# EEE314_PIC32540_Programmer.net
KiCad netlist of a schematic drawn in Altium Designer
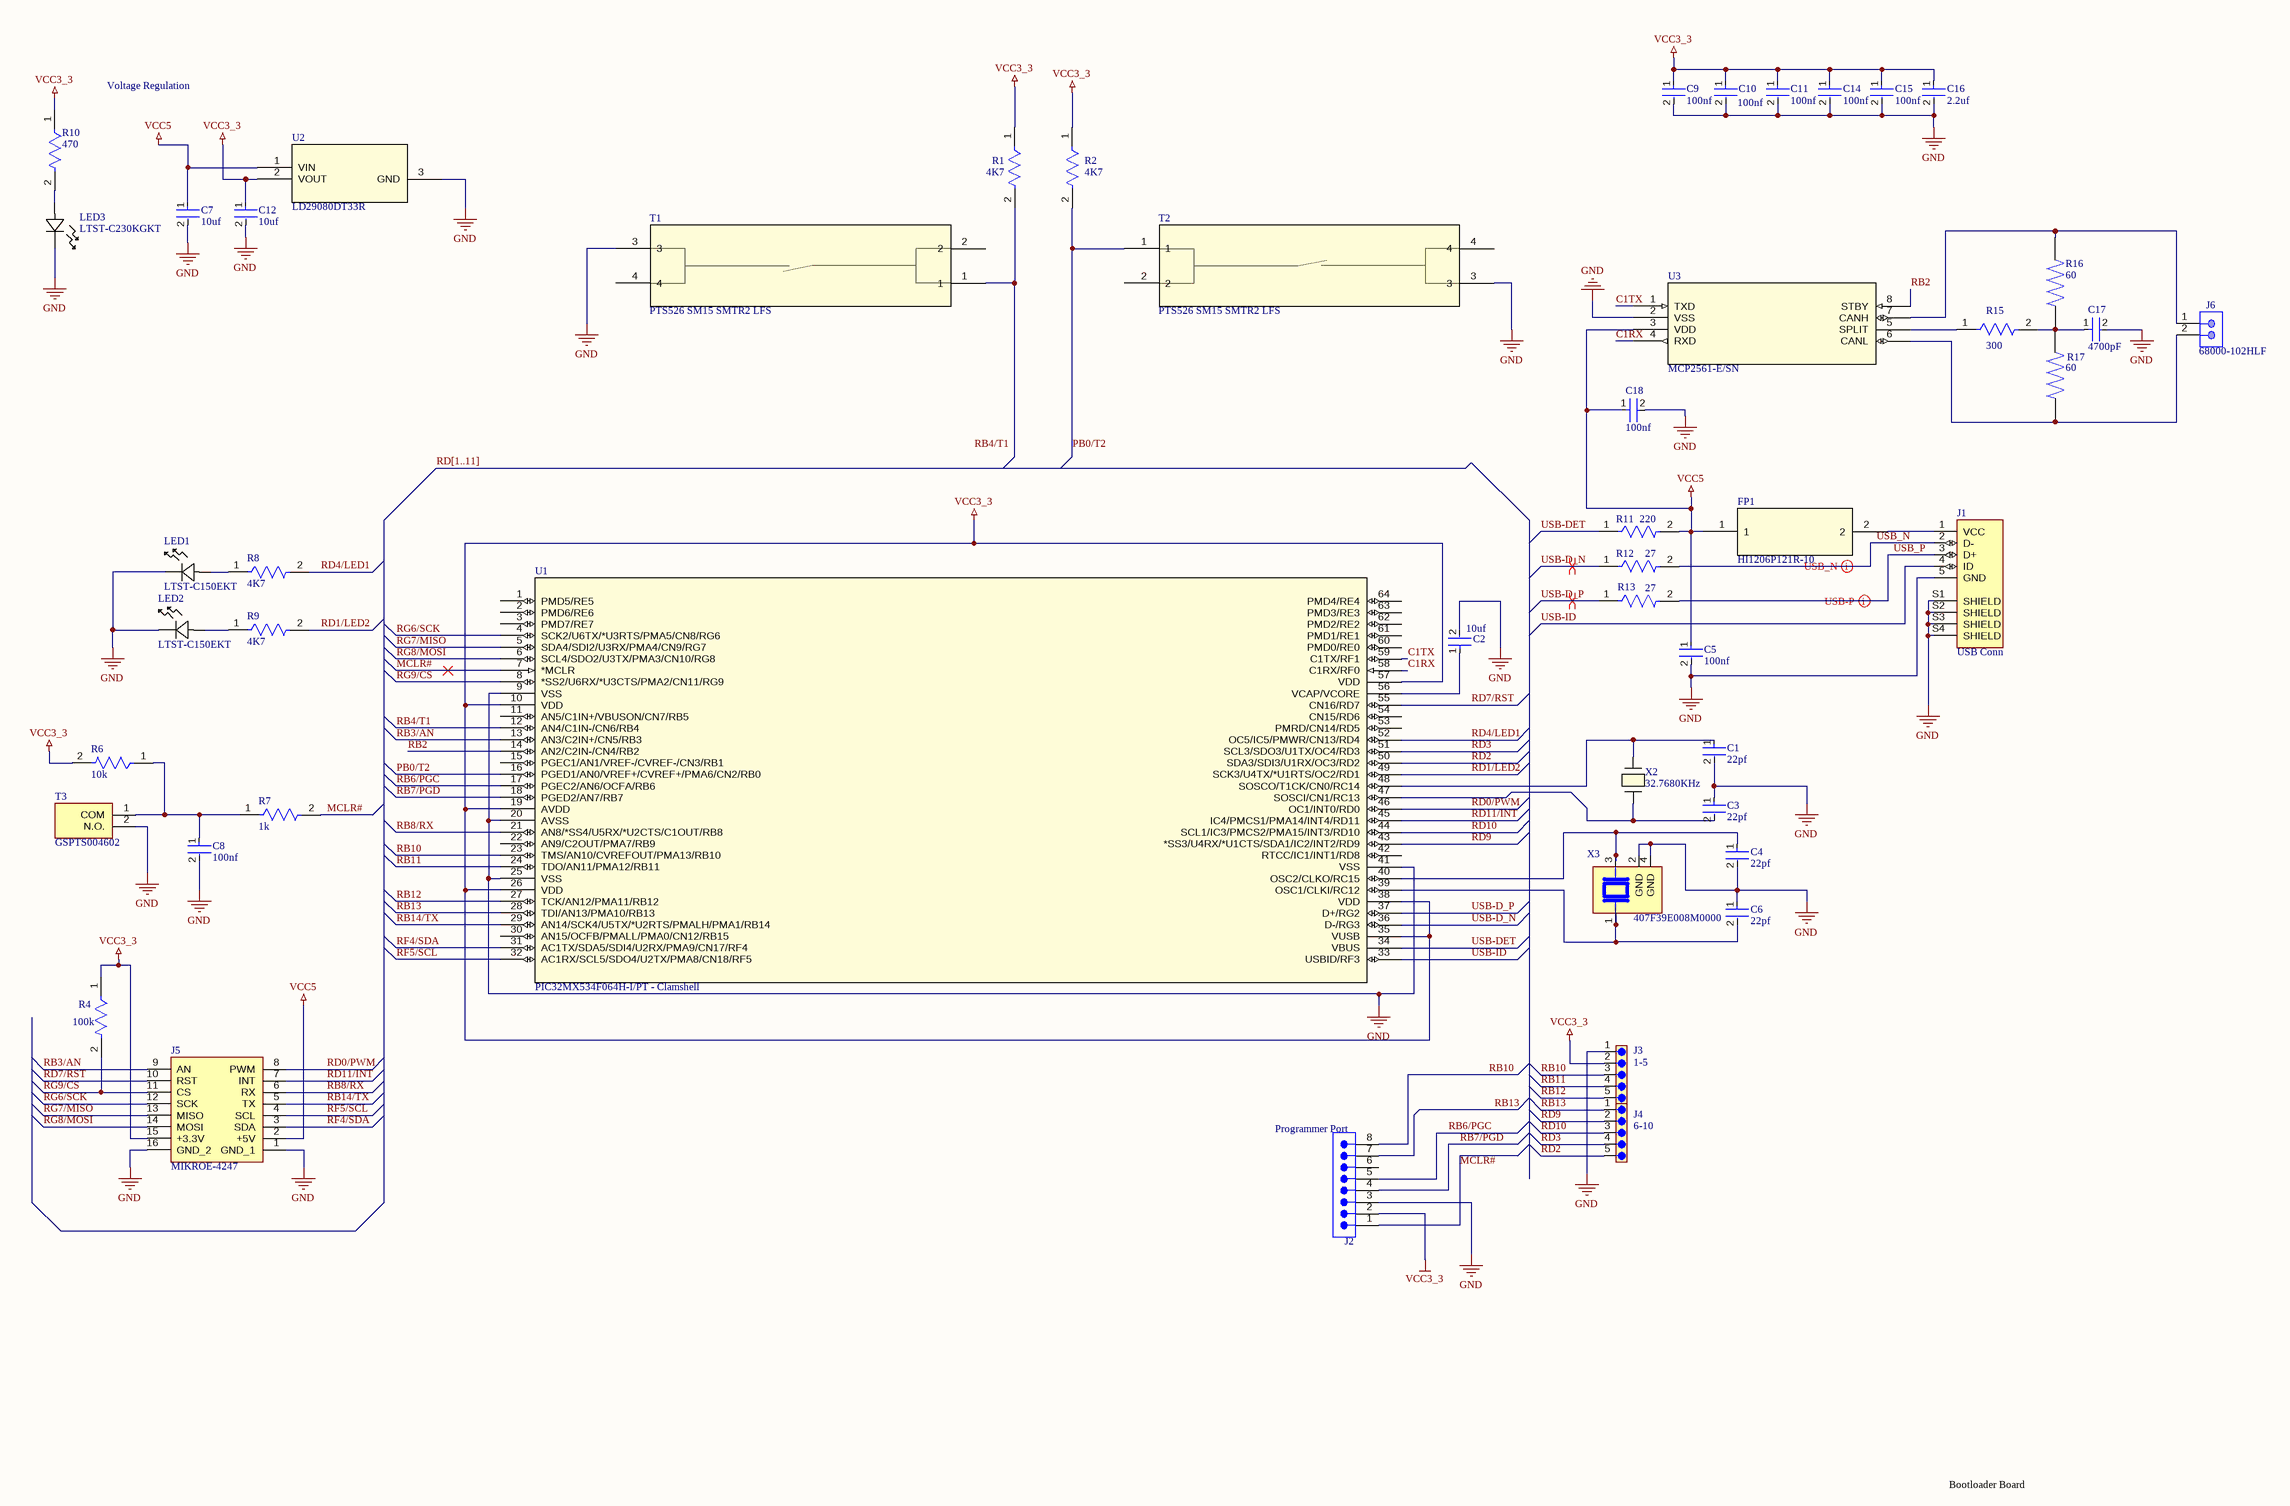
[diagram p0: EEE314 PIC32540 Programmer.SchDoc]

(export (version "E")
  (design (tool "Eeschema 10.0.6"))
  (components
    (comp (ref "C1")
      (value "22pf")
      (footprint "FP-1206-L_3_2_0_2-W_1_6_0-IPC_A")
      (description "Automotive Ceramic Capacitor, 1206, 100nF, 10%, X7R, 15%, 200V")
      (fields (field (name "TOLERANCE") "10%"))
      (libsource (lib "Altium Content Vault") (part "b4654b650e69147ec39a6b967a45e02"))
    )
    (comp (ref "C2")
      (value "10uf")
      (footprint "FP-1206-L_3_2_0_2-W_1_6_0-IPC_A")
      (description "Automotive Ceramic Capacitor, 1206, 100nF, 10%, X7R, 15%, 200V")
      (fields (field (name "TOLERANCE") "10%"))
      (libsource (lib "Altium Content Vault") (part "b4654b650e69147ec39a6b967a45e02"))
    )
    (comp (ref "C3")
      (value "22pf")
      (footprint "FP-1206-L_3_2_0_2-W_1_6_0-IPC_A")
      (description "Automotive Ceramic Capacitor, 1206, 100nF, 10%, X7R, 15%, 200V")
      (fields (field (name "TOLERANCE") "10%"))
      (libsource (lib "Altium Content Vault") (part "b4654b650e69147ec39a6b967a45e02"))
    )
    (comp (ref "C4")
      (value "22pf")
      (footprint "FP-1206-L_3_2_0_2-W_1_6_0-IPC_A")
      (description "Automotive Ceramic Capacitor, 1206, 100nF, 10%, X7R, 15%, 200V")
      (fields (field (name "TOLERANCE") "10%"))
      (libsource (lib "Altium Content Vault") (part "b4654b650e69147ec39a6b967a45e02"))
    )
    (comp (ref "C5")
      (value "100nf")
      (footprint "FP-1206-L_3_2_0_2-W_1_6_0-IPC_A")
      (description "Automotive Ceramic Capacitor, 1206, 100nF, 10%, X7R, 15%, 200V")
      (fields (field (name "TOLERANCE") "10%"))
      (libsource (lib "Altium Content Vault") (part "b4654b650e69147ec39a6b967a45e02"))
    )
    (comp (ref "C6")
      (value "22pf")
      (footprint "FP-1206-L_3_2_0_2-W_1_6_0-IPC_A")
      (description "Automotive Ceramic Capacitor, 1206, 100nF, 10%, X7R, 15%, 200V")
      (fields (field (name "TOLERANCE") "10%"))
      (libsource (lib "Altium Content Vault") (part "b4654b650e69147ec39a6b967a45e02"))
    )
    (comp (ref "C7")
      (value "10uf")
      (footprint "FP-1206-L_3_2_0_2-W_1_6_0-IPC_A")
      (description "Automotive Ceramic Capacitor, 1206, 100nF, 10%, X7R, 15%, 200V")
      (fields (field (name "TOLERANCE") "10%"))
      (libsource (lib "Altium Content Vault") (part "b4654b650e69147ec39a6b967a45e02"))
    )
    (comp (ref "C8")
      (value "100nf")
      (footprint "FP-1206-L_3_2_0_2-W_1_6_0-IPC_A")
      (description "Automotive Ceramic Capacitor, 1206, 100nF, 10%, X7R, 15%, 200V")
      (fields (field (name "TOLERANCE") "10%"))
      (libsource (lib "Altium Content Vault") (part "b4654b650e69147ec39a6b967a45e02"))
    )
    (comp (ref "C9")
      (value "100nf")
      (footprint "FP-1206-L_3_2_0_2-W_1_6_0-IPC_A")
      (description "Automotive Ceramic Capacitor, 1206, 100nF, 10%, X7R, 15%, 200V")
      (fields (field (name "TOLERANCE") "10%"))
      (libsource (lib "Altium Content Vault") (part "b4654b650e69147ec39a6b967a45e02"))
    )
    (comp (ref "C10")
      (value "100nf")
      (footprint "FP-1206-L_3_2_0_2-W_1_6_0-IPC_A")
      (description "Automotive Ceramic Capacitor, 1206, 100nF, 10%, X7R, 15%, 200V")
      (fields (field (name "TOLERANCE") "10%"))
      (libsource (lib "Altium Content Vault") (part "b4654b650e69147ec39a6b967a45e02"))
    )
    (comp (ref "C11")
      (value "100nf")
      (footprint "FP-1206-L_3_2_0_2-W_1_6_0-IPC_A")
      (description "Automotive Ceramic Capacitor, 1206, 100nF, 10%, X7R, 15%, 200V")
      (fields (field (name "TOLERANCE") "10%"))
      (libsource (lib "Altium Content Vault") (part "b4654b650e69147ec39a6b967a45e02"))
    )
    (comp (ref "C12")
      (value "10uf")
      (footprint "FP-1206-L_3_2_0_2-W_1_6_0-IPC_A")
      (description "Automotive Ceramic Capacitor, 1206, 100nF, 10%, X7R, 15%, 200V")
      (fields (field (name "TOLERANCE") "10%"))
      (libsource (lib "Altium Content Vault") (part "b4654b650e69147ec39a6b967a45e02"))
    )
    (comp (ref "C14")
      (value "100nf")
      (footprint "FP-1206-L_3_2_0_2-W_1_6_0-IPC_A")
      (description "Automotive Ceramic Capacitor, 1206, 100nF, 10%, X7R, 15%, 200V")
      (fields (field (name "TOLERANCE") "10%"))
      (libsource (lib "Altium Content Vault") (part "b4654b650e69147ec39a6b967a45e02"))
    )
    (comp (ref "C15")
      (value "100nf")
      (footprint "FP-1206-L_3_2_0_2-W_1_6_0-IPC_A")
      (description "Automotive Ceramic Capacitor, 1206, 100nF, 10%, X7R, 15%, 200V")
      (fields (field (name "TOLERANCE") "10%"))
      (libsource (lib "Altium Content Vault") (part "b4654b650e69147ec39a6b967a45e02"))
    )
    (comp (ref "C16")
      (value "2.2uf")
      (footprint "FP-1206-L_3_2_0_2-W_1_6_0-IPC_A")
      (description "Automotive Ceramic Capacitor, 1206, 100nF, 10%, X7R, 15%, 200V")
      (fields (field (name "TOLERANCE") "10%"))
      (libsource (lib "Altium Content Vault") (part "b4654b650e69147ec39a6b967a45e02"))
    )
    (comp (ref "C17")
      (value "4700pF")
      (footprint "FP-1206-L_3_2_0_2-W_1_6_0-IPC_A")
      (description "Automotive Ceramic Capacitor, 1206, 100nF, 10%, X7R, 15%, 200V")
      (fields (field (name "TOLERANCE") "10%"))
      (libsource (lib "EEE 314 Project 3 EXAMPLE Schematic") (part "CMP-04427-012685-1"))
    )
    (comp (ref "C18")
      (value "100nf")
      (footprint "FP-1206-L_3_2_0_2-W_1_6_0-IPC_A")
      (description "Automotive Ceramic Capacitor, 1206, 100nF, 10%, X7R, 15%, 200V")
      (fields (field (name "TOLERANCE") "10%"))
      (libsource (lib "Altium Content Vault") (part "b4654b650e69147ec39a6b967a45e02"))
    )
    (comp (ref "FP1")
      (value "HI1206P121R-10")
      (footprint "HI1206P121R-10_LRD")
      (description "Description")
      (fields (field (name "COPYRIGHT") "Copyright (C) 2025 Ultra Librarian. All rights reserved."))
      (libsource (lib "Project 3 Schematic Library") (part "HI1206P121R-10"))
    )
    (comp (ref "J1")
      (value "USB Conn")
      (footprint "AMPHENOL_10033526-N3212MLF")
      (fields (field (name "MF") "Amphenol ICC") (field (name "MP") "10033526-N3212MLF"))
      (libsource (lib "10033526-N3212MLF") (part "10033526-N3212MLF"))
    )
    (comp (ref "J2")
      (value "Programmer Port")
      (footprint "61300811021")
      (description "THT Angled Pin Header WR-PHD, Pitch 2.54 mm, Single Row, 8 pins")
      (libsource (lib "Altium Content Vault") (part "Header_Male_1R_08P"))
    )
    (comp (ref "J3")
      (value "1-5")
      (footprint "61300511121")
      (fields
        (field (name "MF") "{'manufacturer': u'~{W}xfcrth Elektronik'}")
        (field (name "MP") "61300511121")
      )
      (libsource (lib "6130XX11121_61300511121") (part "6130XX11121_61300511121"))
    )
    (comp (ref "J4")
      (value "6-10")
      (footprint "61300511121")
      (fields
        (field (name "MF") "{'manufacturer': u'~{W}xfcrth Elektronik'}")
        (field (name "MP") "61300511121")
      )
      (libsource (lib "6130XX11121_61300511121") (part "6130XX11121_61300511121"))
    )
    (comp (ref "J5")
      (value "MIKROE-4247")
      (footprint "MIKROE4247")
      (description "Sockets & Adapters SOCKET mikroBUS 16 TH")
      (fields (field (name "MOUSER PART NUMBER") "932-MIKROE-4247"))
      (libsource (lib "Project 3 Schematic Library") (part "MIKROE-4247"))
    )
    (comp (ref "J6")
      (value "68000-102HLF")
      (footprint "AMPH-68000-102HLF_V")
      (description "Male Header, Pitch 2.54 mm, 1 x 2 Position, Height 8.38 mm, Tail Length 2.41 mm, RoHS, Bulk")
      (fields (field (name "MANUFACTURER") "FCI"))
      (libsource (lib "Altium Content Vault") (part "CN-1P-M-R2"))
    )
    (comp (ref "LED1")
      (value "LTST-C150EKT")
      (footprint "test led")
      (description "Description")
      (fields
        (field (name "MANUFACTURER_PART_NUMBER") "LTST-C150GKT")
        (field (name "COPYRIGHT") "Copyright (C) 2025 Ultra Librarian. All rights reserved.")
      )
      (libsource (lib "Project 3 Schematic Library") (part "test led"))
    )
    (comp (ref "LED2")
      (value "LTST-C150EKT")
      (footprint "test led")
      (description "Description")
      (fields
        (field (name "MANUFACTURER_PART_NUMBER") "LTST-C150GKT")
        (field (name "COPYRIGHT") "Copyright (C) 2025 Ultra Librarian. All rights reserved.")
      )
      (libsource (lib "Project 3 Schematic Library") (part "test led"))
    )
    (comp (ref "LED3")
      (value "LTST-C230KGKT")
      (footprint "LED_LTST-C230KGKT_LTO")
      (description "LED GREEN CLEAR CHIP SMD")
      (fields (field (name "COPYRIGHT") "Copyright (C) 2025 Ultra Librarian. All rights reserved."))
      (libsource (lib "LTST-C230KGKT") (part "LTST-C230KGKT"))
    )
    (comp (ref "R1")
      (value "4K7")
      (footprint "FP-RMCF1206-IPC_A")
      (description "4.7kΩ ±5% 0.25W 1206 Thick Film Chip Resistor AEC-Q200 compliant")
      (fields (field (name "TOLERANCE") "5%"))
      (libsource (lib "Altium Content Vault") (part "1029c3af85768c4190bb7ad29bc67b5"))
    )
    (comp (ref "R2")
      (value "4K7")
      (footprint "FP-RMCF1206-IPC_A")
      (description "4.7kΩ ±5% 0.25W 1206 Thick Film Chip Resistor AEC-Q200 compliant")
      (fields (field (name "TOLERANCE") "5%"))
      (libsource (lib "Altium Content Vault") (part "1029c3af85768c4190bb7ad29bc67b5"))
    )
    (comp (ref "R4")
      (value "100k")
      (footprint "FP-RMCF1206-IPC_A")
      (description "4.7kΩ ±5% 0.25W 1206 Thick Film Chip Resistor AEC-Q200 compliant")
      (fields (field (name "TOLERANCE") "5%"))
      (libsource (lib "Altium Content Vault") (part "1029c3af85768c4190bb7ad29bc67b5"))
    )
    (comp (ref "R6")
      (value "10k")
      (footprint "FP-RMCF1206-IPC_A")
      (description "4.7kΩ ±5% 0.25W 1206 Thick Film Chip Resistor AEC-Q200 compliant")
      (fields (field (name "TOLERANCE") "5%"))
      (libsource (lib "Altium Content Vault") (part "1029c3af85768c4190bb7ad29bc67b5"))
    )
    (comp (ref "R7")
      (value "1k")
      (footprint "FP-RMCF1206-IPC_A")
      (description "4.7kΩ ±5% 0.25W 1206 Thick Film Chip Resistor AEC-Q200 compliant")
      (fields (field (name "TOLERANCE") "5%"))
      (libsource (lib "Altium Content Vault") (part "1029c3af85768c4190bb7ad29bc67b5"))
    )
    (comp (ref "R8")
      (value "4K7")
      (footprint "FP-RMCF1206-IPC_A")
      (description "4.7kΩ ±5% 0.25W 1206 Thick Film Chip Resistor AEC-Q200 compliant")
      (fields (field (name "TOLERANCE") "5%"))
      (libsource (lib "Altium Content Vault") (part "1029c3af85768c4190bb7ad29bc67b5"))
    )
    (comp (ref "R9")
      (value "4K7")
      (footprint "FP-RMCF1206-IPC_A")
      (description "4.7kΩ ±5% 0.25W 1206 Thick Film Chip Resistor AEC-Q200 compliant")
      (fields (field (name "TOLERANCE") "5%"))
      (libsource (lib "Altium Content Vault") (part "1029c3af85768c4190bb7ad29bc67b5"))
    )
    (comp (ref "R10")
      (value "470")
      (footprint "FP-RMCF1206-IPC_A")
      (description "4.7kΩ ±5% 0.25W 1206 Thick Film Chip Resistor AEC-Q200 compliant")
      (fields (field (name "TOLERANCE") "5%"))
      (libsource (lib "Altium Content Vault") (part "1029c3af85768c4190bb7ad29bc67b5"))
    )
    (comp (ref "R11")
      (value "220")
      (footprint "FP-RMCF1206-IPC_A")
      (description "4.7kΩ ±5% 0.25W 1206 Thick Film Chip Resistor AEC-Q200 compliant")
      (fields (field (name "TOLERANCE") "5%"))
      (libsource (lib "Altium Content Vault") (part "1029c3af85768c4190bb7ad29bc67b5"))
    )
    (comp (ref "R12")
      (value "27")
      (footprint "FP-RMCF1206-IPC_A")
      (description "4.7kΩ ±5% 0.25W 1206 Thick Film Chip Resistor AEC-Q200 compliant")
      (fields (field (name "TOLERANCE") "5%"))
      (libsource (lib "Altium Content Vault") (part "1029c3af85768c4190bb7ad29bc67b5"))
    )
    (comp (ref "R13")
      (value "27")
      (footprint "FP-RMCF1206-IPC_A")
      (description "4.7kΩ ±5% 0.25W 1206 Thick Film Chip Resistor AEC-Q200 compliant")
      (fields (field (name "TOLERANCE") "5%"))
      (libsource (lib "Altium Content Vault") (part "1029c3af85768c4190bb7ad29bc67b5"))
    )
    (comp (ref "R15")
      (value "300")
      (footprint "FP-RMCF1206-IPC_B")
      (description "300Ω ±5% 0.25W 1206 Thick Film Chip Resistor AEC-Q200 compliant")
      (fields (field (name "TOLERANCE") "5%"))
      (libsource (lib "Altium Content Vault") (part "1029c3af85768c4190bb7ad29bc67b5"))
    )
    (comp (ref "R16")
      (value "60")
      (footprint "RESC3116X60N")
      (fields (field (name "MF") "Vishay Dale") (field (name "MP") "CRCW120660R0KNEAIF"))
      (libsource (lib "EEE 314 Project 3 EXAMPLE Schematic") (part "CRCW120660R0KNEAIF"))
    )
    (comp (ref "R17")
      (value "60")
      (footprint "RESC3116X60N")
      (fields (field (name "MF") "Vishay Dale") (field (name "MP") "CRCW120660R0KNEAIF"))
      (libsource (lib "EEE 314 Project 3 EXAMPLE Schematic") (part "CRCW120660R0KNEAIF"))
    )
    (comp (ref "T1")
      (value "PTS526 SM15 SMTR2 LFS")
      (footprint "SON4_PTS526 SM15 SMTR2 LFS_CNK")
      (description "Description")
      (fields (field (name "COPYRIGHT") "Copyright (C) 2026 Ultra Librarian. All rights reserved."))
      (libsource (lib "") (part "PTS526 SM15 SMTR2 LFS_1"))
    )
    (comp (ref "T2")
      (value "PTS526 SM15 SMTR2 LFS")
      (footprint "SON4_PTS526 SM15 SMTR2 LFS_CNK")
      (description "Description")
      (fields (field (name "COPYRIGHT") "Copyright (C) 2026 Ultra Librarian. All rights reserved."))
      (libsource (lib "Project 3 Schematic Library") (part "PTS526 SM15 SMTR2 LFS"))
    )
    (comp (ref "T3")
      (value "GSPTS004602")
      (footprint "GSPTS004602")
      (description "Tactile Switch SPST-NO Top Actuated Surface Mount 0.05A,12VDC ,-40C ~ 90C,\"PTS636SK25FSMTR LFS\"")
      (libsource (lib "Project 3 Schematic Library") (part "GSPTS004602_1"))
    )
    (comp (ref "U1")
      (value "PIC32MX534F064H-I/PT - Clamshell")
      (footprint "MCU_64BIT_CLAMSHELL_2x16_2ROWS_1900MILFAR")
      (description "Description")
      (fields
        (field (name "MANUFACTURER_PART_NUMBER") "PIC32MX534F064H-I/PT")
        (field (name "COPYRIGHT") "Copyright (C) 2025 Ultra Librarian. All rights reserved.")
      )
      (libsource (lib "EEE 314 Project 3 EXAMPLE Schematic") (part "PIC32MX534F064H-IPT"))
    )
    (comp (ref "U2")
      (value "LD29080DT33R")
      (footprint "DPAK_STM")
      (description "800 mA fixed and adjustable output very low drop voltage regulator")
      (fields (field (name "COPYRIGHT") "Copyright (C) 2025 Ultra Librarian. All rights reserved."))
      (libsource (lib "Project 3 Schematic Library") (part "LD29080DT33R"))
    )
    (comp (ref "U3")
      (value "MCP2561-E/SN")
      (footprint "SOIC8-N_MC_MCH")
      (description "Description")
      (fields (field (name "COPYRIGHT") "Copyright (C) 2025 Ultra Librarian. All rights reserved."))
      (libsource (lib "EEE 314 Project 3 EXAMPLE Schematic") (part "MCP2561-ESN"))
    )
    (comp (ref "X2")
      (value "32.7680KHz")
      (footprint "XTAL_FC-135_EPS")
      (description "Description")
      (fields
        (field (name "MANUFACTURER_PART_NUMBER") "FC-135 32.7680KA-A5")
        (field (name "COPYRIGHT") "Copyright (C) 2025 Ultra Librarian. All rights reserved.")
      )
      (libsource (lib "Project 3 Schematic Library") (part "FC-135 32.7680KA-A5"))
    )
    (comp (ref "X3")
      (value "407F39E008M0000")
      (footprint "XTAL_407F39E008M0000")
      (description "8 MHz Â±30ppm Crystal 20pF 60 Ohms 4-SMD, No Lead")
      (fields (field (name "MF") "CTS-Frequency Controls"))
      (libsource (lib "Bjorn's Lab") (part "407F39E008M0000"))
    )
  )
  (nets
    (net (code "8") (name "/C1RX") (class "Default")
      (node (ref "U1") (pin "58") (pinfunction "C1RX/RF0_58") (pintype "input"))
      (node (ref "U3") (pin "4") (pinfunction "RXD_4") (pintype "output"))
    )
    (net (code "9") (name "/C1TX") (class "Default")
      (node (ref "U1") (pin "59") (pinfunction "C1TX/RF1_59") (pintype "bidirectional"))
      (node (ref "U3") (pin "1") (pinfunction "TXD_1") (pintype "input"))
    )
    (net (code "10") (name "/MCLR#") (class "Default")
      (node (ref "J2") (pin "1") (pinfunction "1_1") (pintype "passive"))
      (node (ref "R7") (pin "2") (pinfunction "2_2") (pintype "passive"))
      (node (ref "U1") (pin "7") (pinfunction "*MCLR_7") (pintype "input"))
    )
    (net (code "11") (name "/PB0{slash}T2") (class "Default")
      (node (ref "R2") (pin "2") (pinfunction "2_2") (pintype "passive"))
      (node (ref "T2") (pin "1") (pinfunction "1_1") (pintype "passive"))
      (node (ref "U1") (pin "16") (pinfunction "PGED1/AN0/VREF+/CVREF+/PMA6/CN2/RB0_16") (pintype "bidirectional"))
    )
    (net (code "12") (name "/RB2") (class "Default")
      (node (ref "U1") (pin "14") (pinfunction "AN2/C2IN-/CN4/RB2_14") (pintype "bidirectional"))
      (node (ref "U3") (pin "8") (pinfunction "STBY_8") (pintype "input"))
    )
    (net (code "13") (name "/RB3{slash}AN") (class "Default")
      (node (ref "J5") (pin "9") (pinfunction "AN_9") (pintype "passive"))
      (node (ref "U1") (pin "13") (pinfunction "AN3/C2IN+/CN5/RB3_13") (pintype "bidirectional"))
    )
    (net (code "14") (name "/RB4{slash}T1") (class "Default")
      (node (ref "U1") (pin "12") (pinfunction "AN4/C1IN-/CN6/RB4_12") (pintype "bidirectional"))
    )
    (net (code "15") (name "/RB6{slash}PGC") (class "Default")
      (node (ref "J2") (pin "5") (pinfunction "5_5") (pintype "passive"))
      (node (ref "U1") (pin "17") (pinfunction "PGEC2/AN6/OCFA/RB6_17") (pintype "bidirectional"))
    )
    (net (code "16") (name "/RB7{slash}PGD") (class "Default")
      (node (ref "J2") (pin "4") (pinfunction "4_4") (pintype "passive"))
      (node (ref "U1") (pin "18") (pinfunction "PGED2/AN7/RB7_18") (pintype "bidirectional"))
    )
    (net (code "17") (name "/RB8{slash}RX") (class "Default")
      (node (ref "J5") (pin "6") (pinfunction "RX_6") (pintype "passive"))
      (node (ref "U1") (pin "21") (pinfunction "AN8/*SS4/U5RX/*U2CTS/C1OUT/RB8_21") (pintype "bidirectional"))
    )
    (net (code "18") (name "/RB10") (class "Default")
      (node (ref "J2") (pin "8") (pinfunction "8_8") (pintype "passive"))
      (node (ref "J3") (pin "3") (pinfunction "3_3") (pintype "passive"))
      (node (ref "U1") (pin "23") (pinfunction "TMS/AN10/CVREFOUT/PMA13/RB10_23") (pintype "bidirectional"))
    )
    (net (code "19") (name "/RB11") (class "Default")
      (node (ref "J3") (pin "4") (pinfunction "4_4") (pintype "passive"))
      (node (ref "U1") (pin "24") (pinfunction "TDO/AN11/PMA12/RB11_24") (pintype "bidirectional"))
    )
    (net (code "20") (name "/RB12") (class "Default")
      (node (ref "J3") (pin "5") (pinfunction "5_5") (pintype "passive"))
      (node (ref "U1") (pin "27") (pinfunction "TCK/AN12/PMA11/RB12_27") (pintype "bidirectional"))
    )
    (net (code "21") (name "/RB13") (class "Default")
      (node (ref "J2") (pin "7") (pinfunction "7_7") (pintype "passive"))
      (node (ref "J4") (pin "1") (pinfunction "1_1") (pintype "passive"))
      (node (ref "U1") (pin "28") (pinfunction "TDI/AN13/PMA10/RB13_28") (pintype "bidirectional"))
    )
    (net (code "22") (name "/RB14{slash}TX") (class "Default")
      (node (ref "J5") (pin "5") (pinfunction "TX_5") (pintype "passive"))
      (node (ref "U1") (pin "29") (pinfunction "AN14/SCK4/U5TX/*U2RTS/PMALH/PMA1/RB14_29") (pintype "bidirectional"))
    )
    (net (code "23") (name "/RD0{slash}PWM") (class "Default")
      (node (ref "J5") (pin "8") (pinfunction "PWM_8") (pintype "passive"))
      (node (ref "U1") (pin "46") (pinfunction "OC1/INT0/RD0_46") (pintype "bidirectional"))
    )
    (net (code "24") (name "/RD1{slash}LED2") (class "Default")
      (node (ref "R9") (pin "2") (pinfunction "2_2") (pintype "passive"))
      (node (ref "U1") (pin "49") (pinfunction "SCK3/U4TX/*U1RTS/OC2/RD1_49") (pintype "bidirectional"))
    )
    (net (code "25") (name "/RD2") (class "Default")
      (node (ref "J4") (pin "5") (pinfunction "5_5") (pintype "passive"))
      (node (ref "U1") (pin "50") (pinfunction "SDA3/SDI3/U1RX/OC3/RD2_50") (pintype "bidirectional"))
    )
    (net (code "26") (name "/RD3") (class "Default")
      (node (ref "J4") (pin "4") (pinfunction "4_4") (pintype "passive"))
      (node (ref "U1") (pin "51") (pinfunction "SCL3/SDO3/U1TX/OC4/RD3_51") (pintype "bidirectional"))
    )
    (net (code "27") (name "/RD4{slash}LED1") (class "Default")
      (node (ref "R8") (pin "2") (pinfunction "2_2") (pintype "passive"))
      (node (ref "U1") (pin "52") (pinfunction "OC5/IC5/PMWR/CN13/RD4_52") (pintype "bidirectional"))
    )
    (net (code "28") (name "/RD7{slash}RST") (class "Default")
      (node (ref "J5") (pin "10") (pinfunction "RST_10") (pintype "passive"))
      (node (ref "U1") (pin "55") (pinfunction "CN16/RD7_55") (pintype "bidirectional"))
    )
    (net (code "29") (name "/RD9") (class "Default")
      (node (ref "J4") (pin "2") (pinfunction "2_2") (pintype "passive"))
      (node (ref "U1") (pin "43") (pinfunction "*SS3/U4RX/*U1CTS/SDA1/IC2/INT2/RD9_43") (pintype "bidirectional"))
    )
    (net (code "30") (name "/RD10") (class "Default")
      (node (ref "J4") (pin "3") (pinfunction "3_3") (pintype "passive"))
      (node (ref "U1") (pin "44") (pinfunction "SCL1/IC3/PMCS2/PMA15/INT3/RD10_44") (pintype "bidirectional"))
    )
    (net (code "31") (name "/RD11{slash}INT") (class "Default")
      (node (ref "J5") (pin "7") (pinfunction "INT_7") (pintype "passive"))
      (node (ref "U1") (pin "45") (pinfunction "IC4/PMCS1/PMA14/INT4/RD11_45") (pintype "bidirectional"))
    )
    (net (code "33") (name "/RF4{slash}SDA") (class "Default")
      (node (ref "J5") (pin "3") (pinfunction "SDA_3") (pintype "passive"))
      (node (ref "U1") (pin "31") (pinfunction "AC1TX/SDA5/SDI4/U2RX/PMA9/CN17/RF4_31") (pintype "bidirectional"))
    )
    (net (code "34") (name "/RF5{slash}SCL") (class "Default")
      (node (ref "J5") (pin "4") (pinfunction "SCL_4") (pintype "passive"))
      (node (ref "U1") (pin "32") (pinfunction "AC1RX/SCL5/SDO4/U2TX/PMA8/CN18/RF5_32") (pintype "bidirectional"))
    )
    (net (code "35") (name "/RG6{slash}SCK") (class "Default")
      (node (ref "J5") (pin "12") (pinfunction "SCK_12") (pintype "passive"))
      (node (ref "U1") (pin "4") (pinfunction "SCK2/U6TX/*U3RTS/PMA5/CN8/RG6_4") (pintype "bidirectional"))
    )
    (net (code "36") (name "/RG7{slash}MISO") (class "Default")
      (node (ref "J5") (pin "13") (pinfunction "MISO_13") (pintype "passive"))
      (node (ref "U1") (pin "5") (pinfunction "SDA4/SDI2/U3RX/PMA4/CN9/RG7_5") (pintype "bidirectional"))
    )
    (net (code "37") (name "/RG8{slash}MOSI") (class "Default")
      (node (ref "J5") (pin "14") (pinfunction "MOSI_14") (pintype "passive"))
      (node (ref "U1") (pin "6") (pinfunction "SCL4/SDO2/U3TX/PMA3/CN10/RG8_6") (pintype "bidirectional"))
    )
    (net (code "38") (name "/RG9{slash}CS") (class "Default")
      (node (ref "J5") (pin "11") (pinfunction "CS_11") (pintype "passive"))
      (node (ref "R4") (pin "2") (pinfunction "2_2") (pintype "passive"))
      (node (ref "U1") (pin "8") (pinfunction "*SS2/U6RX/*U3CTS/PMA2/CN11/RG9_8") (pintype "bidirectional"))
    )
    (net (code "39") (name "/USB-DET") (class "Default")
      (node (ref "R11") (pin "1") (pinfunction "1_1") (pintype "passive"))
      (node (ref "U1") (pin "34") (pinfunction "VBUS_34") (pintype "power_in"))
    )
    (net (code "40") (name "/USB-D_N") (class "Default")
      (node (ref "R12") (pin "1") (pinfunction "1_1") (pintype "passive"))
      (node (ref "U1") (pin "36") (pinfunction "D-/RG3_36") (pintype "bidirectional"))
    )
    (net (code "41") (name "/USB-D_P") (class "Default")
      (node (ref "R13") (pin "1") (pinfunction "1_1") (pintype "passive"))
      (node (ref "U1") (pin "37") (pinfunction "D+/RG2_37") (pintype "bidirectional"))
    )
    (net (code "42") (name "/USB-ID") (class "Default")
      (node (ref "J1") (pin "4") (pinfunction "ID_4") (pintype "bidirectional"))
      (node (ref "U1") (pin "33") (pinfunction "USBID/RF3_33") (pintype "bidirectional"))
    )
    (net (code "43") (name "/USB_N") (class "Default")
      (node (ref "J1") (pin "2") (pinfunction "D-_2") (pintype "bidirectional"))
      (node (ref "R12") (pin "2") (pinfunction "2_2") (pintype "passive"))
    )
    (net (code "44") (name "/USB_P") (class "Default")
      (node (ref "J1") (pin "3") (pinfunction "D+_3") (pintype "bidirectional"))
      (node (ref "R13") (pin "2") (pinfunction "2_2") (pintype "passive"))
    )
    (net (code "45") (name "GND") (class "Default")
      (node (ref "C1") (pin "2") (pinfunction "2_2") (pintype "passive"))
      (node (ref "C10") (pin "2") (pinfunction "2_2") (pintype "passive"))
      (node (ref "C11") (pin "2") (pinfunction "2_2") (pintype "passive"))
      (node (ref "C12") (pin "2") (pinfunction "2_2") (pintype "passive"))
      (node (ref "C14") (pin "2") (pinfunction "2_2") (pintype "passive"))
      (node (ref "C15") (pin "2") (pinfunction "2_2") (pintype "passive"))
      (node (ref "C16") (pin "2") (pinfunction "2_2") (pintype "passive"))
      (node (ref "C17") (pin "2") (pinfunction "2_2") (pintype "passive"))
      (node (ref "C18") (pin "2") (pinfunction "2_2") (pintype "passive"))
      (node (ref "C2") (pin "2") (pinfunction "2_2") (pintype "passive"))
      (node (ref "C3") (pin "1") (pinfunction "1_1") (pintype "passive"))
      (node (ref "C4") (pin "2") (pinfunction "2_2") (pintype "passive"))
      (node (ref "C5") (pin "2") (pinfunction "2_2") (pintype "passive"))
      (node (ref "C6") (pin "1") (pinfunction "1_1") (pintype "passive"))
      (node (ref "C7") (pin "2") (pinfunction "2_2") (pintype "passive"))
      (node (ref "C8") (pin "2") (pinfunction "2_2") (pintype "passive"))
      (node (ref "C9") (pin "2") (pinfunction "2_2") (pintype "passive"))
      (node (ref "J1") (pin "5") (pinfunction "GND_5") (pintype "power_in"))
      (node (ref "J1") (pin "S1") (pinfunction "SHIELD_S1") (pintype "passive"))
      (node (ref "J1") (pin "S2") (pinfunction "SHIELD_S2") (pintype "passive"))
      (node (ref "J1") (pin "S3") (pinfunction "SHIELD_S3") (pintype "passive"))
      (node (ref "J1") (pin "S4") (pinfunction "SHIELD_S4") (pintype "passive"))
      (node (ref "J2") (pin "3") (pinfunction "3_3") (pintype "passive"))
      (node (ref "J3") (pin "1") (pinfunction "1_1") (pintype "passive"))
      (node (ref "J5") (pin "1") (pinfunction "GND_1_1") (pintype "passive"))
      (node (ref "J5") (pin "16") (pinfunction "GND_2_16") (pintype "passive"))
      (node (ref "LED1") (pin "1") (pinfunction "1_1") (pintype "passive"))
      (node (ref "LED2") (pin "1") (pinfunction "1_1") (pintype "passive"))
      (node (ref "LED3") (pin "1") (pinfunction "1_1") (pintype "passive"))
      (node (ref "T1") (pin "3") (pinfunction "3_3") (pintype "passive"))
      (node (ref "T2") (pin "3") (pinfunction "3_3") (pintype "passive"))
      (node (ref "T3") (pin "2") (pinfunction "N.O._2") (pintype "passive"))
      (node (ref "U1") (pin "20") (pinfunction "AVSS_20") (pintype "power_in"))
      (node (ref "U1") (pin "25") (pinfunction "VSS_25") (pintype "power_in"))
      (node (ref "U1") (pin "41") (pinfunction "VSS_41") (pintype "power_in"))
      (node (ref "U1") (pin "9") (pinfunction "VSS_9") (pintype "power_in"))
      (node (ref "U2") (pin "3") (pinfunction "GND_3") (pintype "power_in"))
      (node (ref "U3") (pin "2") (pinfunction "VSS_2") (pintype "power_in"))
      (node (ref "X3") (pin "2") (pinfunction "GND_2") (pintype "power_in"))
      (node (ref "X3") (pin "4") (pinfunction "GND_4") (pintype "power_in"))
    )
    (net (code "46") (name "Net-(C17-Pad1)") (class "Default")
      (node (ref "C17") (pin "1") (pinfunction "1_1") (pintype "passive"))
      (node (ref "R15") (pin "2") (pinfunction "2_2") (pintype "passive"))
      (node (ref "R16") (pin "1") (pinfunction "1_1") (pintype "passive"))
      (node (ref "R17") (pin "2") (pinfunction "2_2") (pintype "passive"))
    )
    (net (code "47") (name "Net-(J1-VCC)") (class "Default")
      (node (ref "FP1") (pin "2") (pinfunction "2_2") (pintype "passive"))
      (node (ref "J1") (pin "1") (pinfunction "VCC_1") (pintype "power_in"))
    )
    (net (code "48") (name "Net-(LED1-Pad2)") (class "Default")
      (node (ref "LED1") (pin "2") (pinfunction "2_2") (pintype "passive"))
      (node (ref "R8") (pin "1") (pinfunction "1_1") (pintype "passive"))
    )
    (net (code "49") (name "Net-(LED2-Pad2)") (class "Default")
      (node (ref "LED2") (pin "2") (pinfunction "2_2") (pintype "passive"))
      (node (ref "R9") (pin "1") (pinfunction "1_1") (pintype "passive"))
    )
    (net (code "50") (name "Net-(LED3-Pad2)") (class "Default")
      (node (ref "LED3") (pin "2") (pinfunction "2_2") (pintype "passive"))
      (node (ref "R10") (pin "2") (pinfunction "2_2") (pintype "passive"))
    )
    (net (code "51") (name "Net-(R1-Pad2)") (class "Default")
      (node (ref "R1") (pin "2") (pinfunction "2_2") (pintype "passive"))
      (node (ref "T1") (pin "1") (pinfunction "1_1") (pintype "passive"))
    )
    (net (code "52") (name "Net-(T3-COM)") (class "Default")
      (node (ref "C8") (pin "1") (pinfunction "1_1") (pintype "passive"))
      (node (ref "R6") (pin "1") (pinfunction "1_1") (pintype "passive"))
      (node (ref "R7") (pin "1") (pinfunction "1_1") (pintype "passive"))
      (node (ref "T3") (pin "1") (pinfunction "COM_1") (pintype "passive"))
    )
    (net (code "53") (name "Net-(U1-OSC1{slash}CLKI{slash}RC12)") (class "Default")
      (node (ref "C6") (pin "2") (pinfunction "2_2") (pintype "passive"))
      (node (ref "U1") (pin "39") (pinfunction "OSC1/CLKI/RC12_39") (pintype "bidirectional"))
      (node (ref "X3") (pin "1") (pinfunction "1_1") (pintype "passive"))
    )
    (net (code "54") (name "Net-(U1-OSC2{slash}CLKO{slash}RC15)") (class "Default")
      (node (ref "C4") (pin "1") (pinfunction "1_1") (pintype "passive"))
      (node (ref "U1") (pin "40") (pinfunction "OSC2/CLKO/RC15_40") (pintype "bidirectional"))
      (node (ref "X3") (pin "3") (pinfunction "2_3") (pintype "passive"))
    )
    (net (code "55") (name "Net-(U1-SOSCI{slash}CN1{slash}RC13)") (class "Default")
      (node (ref "C3") (pin "2") (pinfunction "2_2") (pintype "passive"))
      (node (ref "U1") (pin "47") (pinfunction "SOSCI/CN1/RC13_47") (pintype "bidirectional"))
      (node (ref "X2") (pin "1") (pinfunction "1_1") (pintype "passive"))
    )
    (net (code "56") (name "Net-(U1-SOSCO{slash}T1CK{slash}CN0{slash}RC14)") (class "Default")
      (node (ref "C1") (pin "1") (pinfunction "1_1") (pintype "passive"))
      (node (ref "U1") (pin "48") (pinfunction "SOSCO/T1CK/CN0/RC14_48") (pintype "bidirectional"))
      (node (ref "X2") (pin "2") (pinfunction "2_2") (pintype "passive"))
    )
    (net (code "57") (name "Net-(U1-VCAP{slash}VCORE)") (class "Default")
      (node (ref "C2") (pin "1") (pinfunction "1_1") (pintype "passive"))
      (node (ref "U1") (pin "56") (pinfunction "VCAP/VCORE_56") (pintype "power_in"))
    )
    (net (code "58") (name "Net-(U3-CANH)") (class "Default")
      (node (ref "J6") (pin "1") (pinfunction "1_1") (pintype "passive"))
      (node (ref "R16") (pin "2") (pinfunction "2_2") (pintype "passive"))
      (node (ref "U3") (pin "7") (pinfunction "CANH_7") (pintype "bidirectional"))
    )
    (net (code "59") (name "Net-(U3-CANL)") (class "Default")
      (node (ref "J6") (pin "2") (pinfunction "2_2") (pintype "passive"))
      (node (ref "R17") (pin "1") (pinfunction "1_1") (pintype "passive"))
      (node (ref "U3") (pin "6") (pinfunction "CANL_6") (pintype "bidirectional"))
    )
    (net (code "60") (name "Net-(U3-SPLIT)") (class "Default")
      (node (ref "R15") (pin "1") (pinfunction "1_1") (pintype "passive"))
      (node (ref "U3") (pin "5") (pinfunction "SPLIT_5") (pintype "passive"))
    )
    (net (code "61") (name "VCC3_3") (class "Default")
      (node (ref "C10") (pin "1") (pinfunction "1_1") (pintype "passive"))
      (node (ref "C11") (pin "1") (pinfunction "1_1") (pintype "passive"))
      (node (ref "C12") (pin "1") (pinfunction "1_1") (pintype "passive"))
      (node (ref "C14") (pin "1") (pinfunction "1_1") (pintype "passive"))
      (node (ref "C15") (pin "1") (pinfunction "1_1") (pintype "passive"))
      (node (ref "C16") (pin "1") (pinfunction "1_1") (pintype "passive"))
      (node (ref "C9") (pin "1") (pinfunction "1_1") (pintype "passive"))
      (node (ref "J2") (pin "2") (pinfunction "2_2") (pintype "passive"))
      (node (ref "J3") (pin "2") (pinfunction "2_2") (pintype "passive"))
      (node (ref "J5") (pin "15") (pinfunction "+3.3V_15") (pintype "passive"))
      (node (ref "R1") (pin "1") (pinfunction "1_1") (pintype "passive"))
      (node (ref "R10") (pin "1") (pinfunction "1_1") (pintype "passive"))
      (node (ref "R2") (pin "1") (pinfunction "1_1") (pintype "passive"))
      (node (ref "R4") (pin "1") (pinfunction "1_1") (pintype "passive"))
      (node (ref "R6") (pin "2") (pinfunction "2_2") (pintype "passive"))
      (node (ref "U1") (pin "10") (pinfunction "VDD_10") (pintype "power_in"))
      (node (ref "U1") (pin "19") (pinfunction "AVDD_19") (pintype "power_in"))
      (node (ref "U1") (pin "26") (pinfunction "VDD_26") (pintype "power_in"))
      (node (ref "U1") (pin "35") (pinfunction "VUSB_35") (pintype "power_in"))
      (node (ref "U1") (pin "38") (pinfunction "VDD_38") (pintype "power_in"))
      (node (ref "U1") (pin "57") (pinfunction "VDD_57") (pintype "power_in"))
      (node (ref "U2") (pin "2") (pinfunction "VOUT_2") (pintype "power_in"))
    )
    (net (code "62") (name "VCC5") (class "Default")
      (node (ref "C18") (pin "1") (pinfunction "1_1") (pintype "passive"))
      (node (ref "C5") (pin "1") (pinfunction "1_1") (pintype "passive"))
      (node (ref "C7") (pin "1") (pinfunction "1_1") (pintype "passive"))
      (node (ref "FP1") (pin "1") (pinfunction "1_1") (pintype "passive"))
      (node (ref "J5") (pin "2") (pinfunction "+5V_2") (pintype "passive"))
      (node (ref "R11") (pin "2") (pinfunction "2_2") (pintype "passive"))
      (node (ref "U2") (pin "1") (pinfunction "VIN_1") (pintype "power_in"))
      (node (ref "U3") (pin "3") (pinfunction "VDD_3") (pintype "power_in"))
    )
    (net (code "63") (name "unconnected-(J2-Pad6)") (class "Default")
      (node (ref "J2") (pin "6") (pinfunction "6_6") (pintype "passive"))
    )
    (net (code "64") (name "unconnected-(T1-Pad2)") (class "Default")
      (node (ref "T1") (pin "2") (pinfunction "2_2") (pintype "passive"))
    )
    (net (code "65") (name "unconnected-(T1-Pad4)") (class "Default")
      (node (ref "T1") (pin "4") (pinfunction "4_4") (pintype "passive"))
    )
    (net (code "66") (name "unconnected-(T2-Pad2)") (class "Default")
      (node (ref "T2") (pin "2") (pinfunction "2_2") (pintype "passive"))
    )
    (net (code "67") (name "unconnected-(T2-Pad4)") (class "Default")
      (node (ref "T2") (pin "4") (pinfunction "4_4") (pintype "passive"))
    )
    (net (code "68") (name "unconnected-(U1-AN5{slash}C1IN+{slash}VBUSON{slash}CN7{slash}RB5-Pad11)") (class "Default")
      (node (ref "U1") (pin "11") (pinfunction "AN5/C1IN+/VBUSON/CN7/RB5_11") (pintype "bidirectional"))
    )
    (net (code "69") (name "unconnected-(U1-AN9{slash}C2OUT{slash}PMA7{slash}RB9-Pad22)") (class "Default")
      (node (ref "U1") (pin "22") (pinfunction "AN9/C2OUT/PMA7/RB9_22") (pintype "bidirectional"))
    )
    (net (code "70") (name "unconnected-(U1-AN15{slash}OCFB{slash}PMALL{slash}PMA0{slash}CN12{slash}RB15-Pad30)") (class "Default")
      (node (ref "U1") (pin "30") (pinfunction "AN15/OCFB/PMALL/PMA0/CN12/RB15_30") (pintype "bidirectional"))
    )
    (net (code "71") (name "unconnected-(U1-CN15{slash}RD6-Pad54)") (class "Default")
      (node (ref "U1") (pin "54") (pinfunction "CN15/RD6_54") (pintype "bidirectional"))
    )
    (net (code "72") (name "unconnected-(U1-PGEC1{slash}AN1{slash}VREF-{slash}CVREF-{slash}CN3{slash}RB1-Pad15)") (class "Default")
      (node (ref "U1") (pin "15") (pinfunction "PGEC1/AN1/VREF-/CVREF-/CN3/RB1_15") (pintype "bidirectional"))
    )
    (net (code "73") (name "unconnected-(U1-PMD0{slash}RE0-Pad60)") (class "Default")
      (node (ref "U1") (pin "60") (pinfunction "PMD0/RE0_60") (pintype "bidirectional"))
    )
    (net (code "74") (name "unconnected-(U1-PMD1{slash}RE1-Pad61)") (class "Default")
      (node (ref "U1") (pin "61") (pinfunction "PMD1/RE1_61") (pintype "bidirectional"))
    )
    (net (code "75") (name "unconnected-(U1-PMD2{slash}RE2-Pad62)") (class "Default")
      (node (ref "U1") (pin "62") (pinfunction "PMD2/RE2_62") (pintype "bidirectional"))
    )
    (net (code "76") (name "unconnected-(U1-PMD3{slash}RE3-Pad63)") (class "Default")
      (node (ref "U1") (pin "63") (pinfunction "PMD3/RE3_63") (pintype "bidirectional"))
    )
    (net (code "77") (name "unconnected-(U1-PMD4{slash}RE4-Pad64)") (class "Default")
      (node (ref "U1") (pin "64") (pinfunction "PMD4/RE4_64") (pintype "bidirectional"))
    )
    (net (code "78") (name "unconnected-(U1-PMD5{slash}RE5-Pad1)") (class "Default")
      (node (ref "U1") (pin "1") (pinfunction "PMD5/RE5_1") (pintype "bidirectional"))
    )
    (net (code "79") (name "unconnected-(U1-PMD6{slash}RE6-Pad2)") (class "Default")
      (node (ref "U1") (pin "2") (pinfunction "PMD6/RE6_2") (pintype "bidirectional"))
    )
    (net (code "80") (name "unconnected-(U1-PMD7{slash}RE7-Pad3)") (class "Default")
      (node (ref "U1") (pin "3") (pinfunction "PMD7/RE7_3") (pintype "bidirectional"))
    )
    (net (code "81") (name "unconnected-(U1-PMRD{slash}CN14{slash}RD5-Pad53)") (class "Default")
      (node (ref "U1") (pin "53") (pinfunction "PMRD/CN14/RD5_53") (pintype "bidirectional"))
    )
    (net (code "82") (name "unconnected-(U1-RTCC{slash}IC1{slash}INT1{slash}RD8-Pad42)") (class "Default")
      (node (ref "U1") (pin "42") (pinfunction "RTCC/IC1/INT1/RD8_42") (pintype "bidirectional"))
    )
  )
)
